# Mainboard_PWR_Board_Connector.net
KiCad netlist of a schematic drawn in Altium Designer
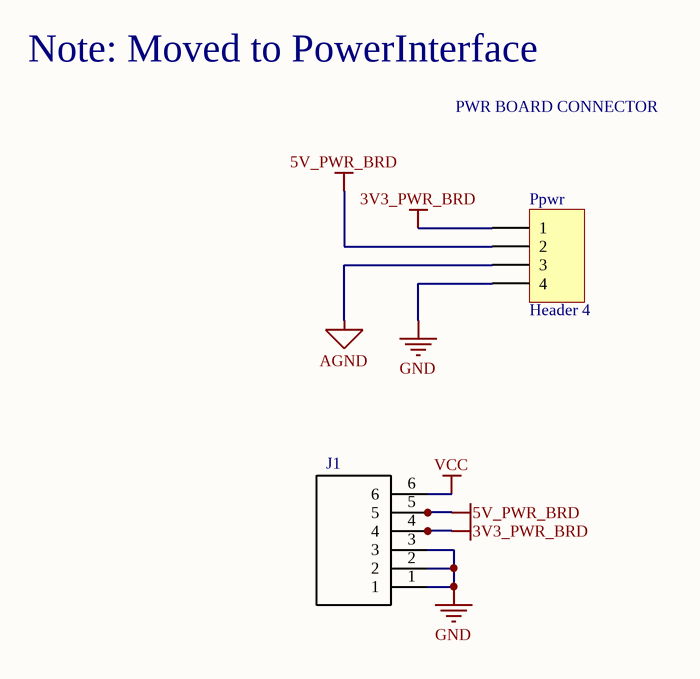
[diagram p0: Mainboard_PWR Board Connector.SchDoc]

(export (version "E")
  (design (tool "Eeschema 10.0.6"))
  (components
    (comp (ref "J1")
      (value "CN HEADER VERT 6POS 3.96MM")
      (footprint "CN HDR 6POS 3.96MM")
      (description "Connector Header Through Hole 6 position 0.156\" (3.96mm)")
      (fields (field (name "MF") "TE Connectivity") (field (name "MP") "1877285-6"))
      (libsource (lib "AltiumLibraries") (part "CN HDR VERT 6POS 3.96MM"))
    )
    (comp (ref "Ppwr")
      (value "Header 4")
      (footprint "HDR1X4")
      (description "Header, 4-Pin")
      (fields (field (name "PUBLISHER") "Altium Limited"))
      (libsource (lib "Miscellaneous Connectors") (part "Header 4"))
    )
  )
  (nets
    (net (code "1") (name "3V3_PWR_BRD") (class "Default")
      (node (ref "J1") (pin "4") (pinfunction "4_4") (pintype "passive"))
      (node (ref "Ppwr") (pin "1") (pinfunction "1_1") (pintype "passive"))
    )
    (net (code "2") (name "5V_PWR_BRD") (class "Default")
      (node (ref "J1") (pin "5") (pinfunction "5_5") (pintype "passive"))
      (node (ref "Ppwr") (pin "2") (pinfunction "2_2") (pintype "passive"))
    )
    (net (code "3") (name "AGND") (class "Default")
      (node (ref "Ppwr") (pin "3") (pinfunction "3_3") (pintype "passive"))
    )
    (net (code "4") (name "GND") (class "Default")
      (node (ref "J1") (pin "1") (pinfunction "1_1") (pintype "passive"))
      (node (ref "J1") (pin "2") (pinfunction "2_2") (pintype "passive"))
      (node (ref "J1") (pin "3") (pinfunction "3_3") (pintype "passive"))
      (node (ref "Ppwr") (pin "4") (pinfunction "4_4") (pintype "passive"))
    )
    (net (code "5") (name "VCC") (class "Default")
      (node (ref "J1") (pin "6") (pinfunction "6_6") (pintype "passive"))
    )
  )
)
